# ArduinoInterface.net
KiCad netlist of a schematic drawn in EAGLE
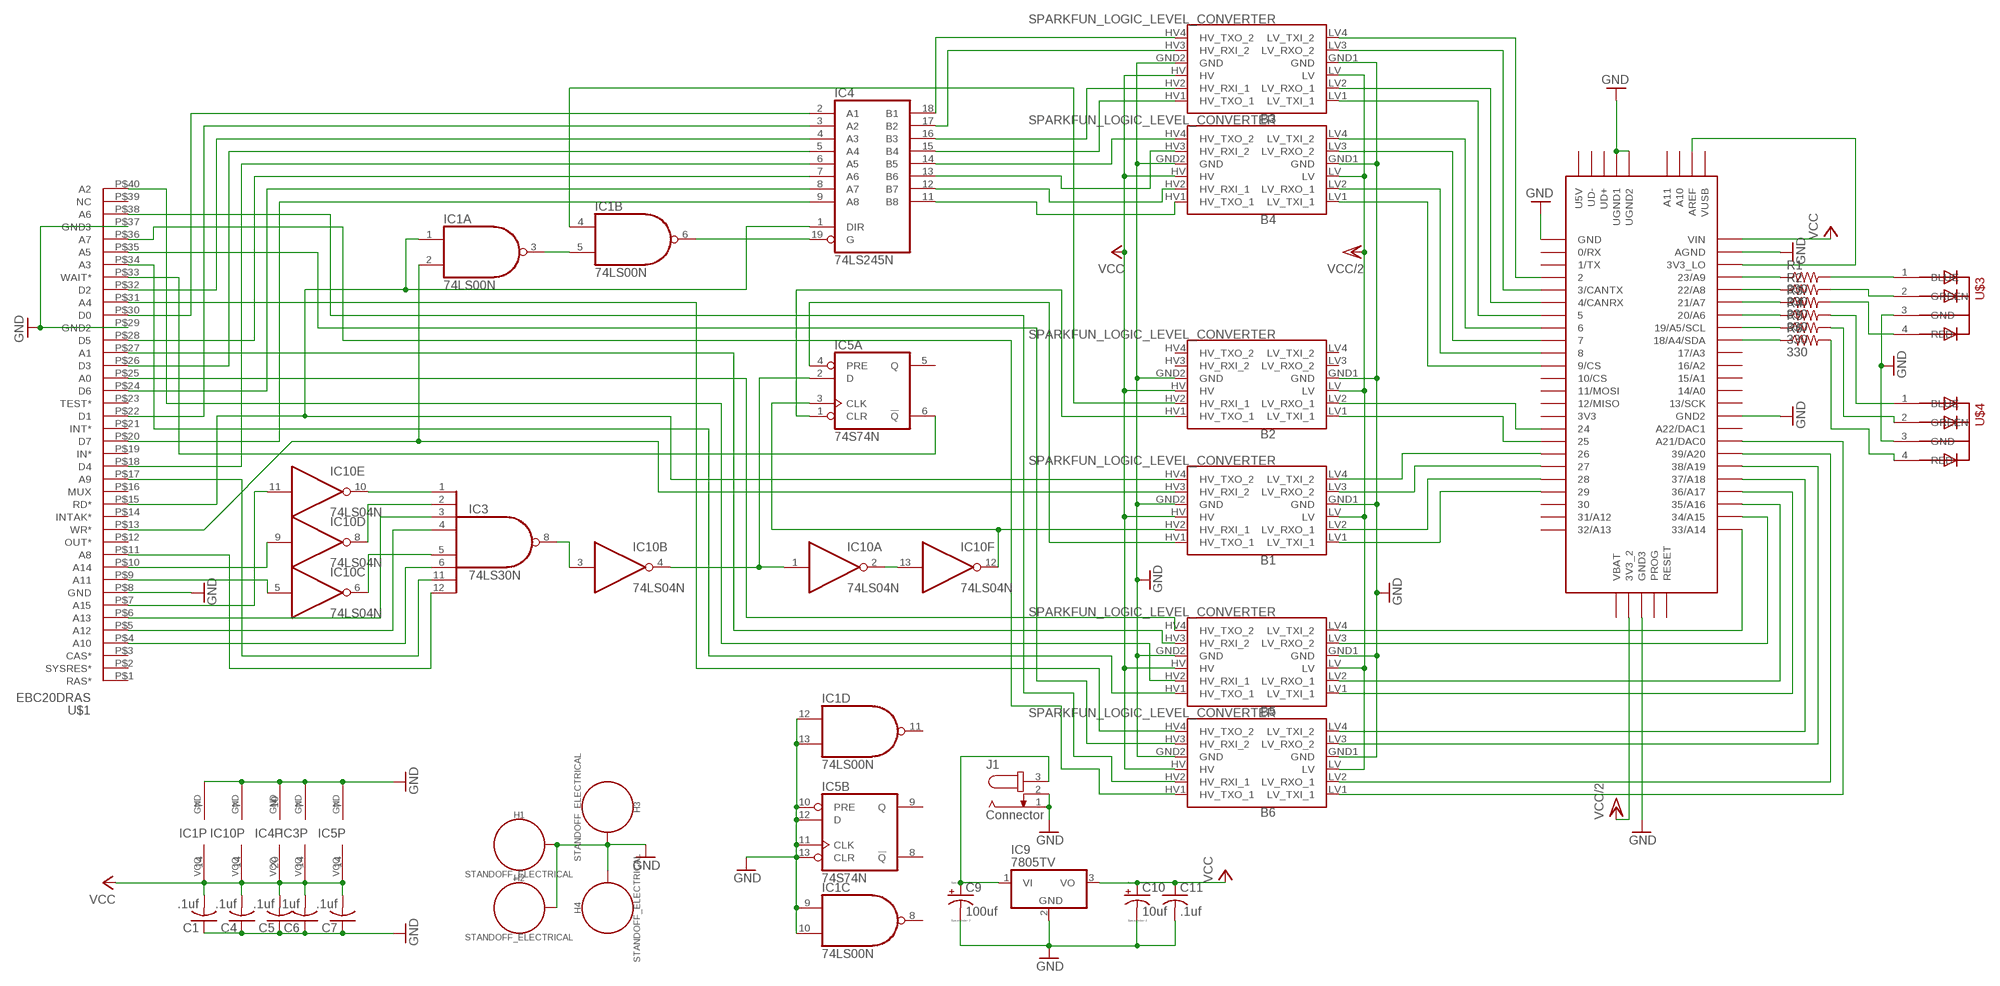
[diagram p0: schematic, sheet 1]

(export (version "E")
  (design (tool "Eeschema 10.0.6"))
  (components
    (comp (ref "B1")
      (value "SPARKFUN_LOGIC_LEVEL_CONVERTER")
      (footprint "eagle-import:SPARKFUN_LOGIC_LEVEL_CONVERTER")
      (libsource (lib "eagle-import") (part "SPARKFUN_LOGIC_LEVEL_CONVERTER"))
    )
    (comp (ref "B2")
      (value "SPARKFUN_LOGIC_LEVEL_CONVERTER")
      (footprint "eagle-import:SPARKFUN_LOGIC_LEVEL_CONVERTER")
      (libsource (lib "eagle-import") (part "SPARKFUN_LOGIC_LEVEL_CONVERTER"))
    )
    (comp (ref "B3")
      (value "SPARKFUN_LOGIC_LEVEL_CONVERTER")
      (footprint "eagle-import:SPARKFUN_LOGIC_LEVEL_CONVERTER")
      (libsource (lib "eagle-import") (part "SPARKFUN_LOGIC_LEVEL_CONVERTER"))
    )
    (comp (ref "B4")
      (value "SPARKFUN_LOGIC_LEVEL_CONVERTER")
      (footprint "eagle-import:SPARKFUN_LOGIC_LEVEL_CONVERTER")
      (libsource (lib "eagle-import") (part "SPARKFUN_LOGIC_LEVEL_CONVERTER"))
    )
    (comp (ref "B5")
      (value "SPARKFUN_LOGIC_LEVEL_CONVERTER")
      (footprint "eagle-import:SPARKFUN_LOGIC_LEVEL_CONVERTER")
      (libsource (lib "eagle-import") (part "SPARKFUN_LOGIC_LEVEL_CONVERTER"))
    )
    (comp (ref "B6")
      (value "SPARKFUN_LOGIC_LEVEL_CONVERTER")
      (footprint "eagle-import:SPARKFUN_LOGIC_LEVEL_CONVERTER")
      (libsource (lib "eagle-import") (part "SPARKFUN_LOGIC_LEVEL_CONVERTER"))
    )
    (comp (ref "C1")
      (value ".1uf")
      (footprint "eagle-import:C025-025X050")
      (libsource (lib "eagle-import") (part "C-US025-025X050"))
    )
    (comp (ref "C4")
      (value ".1uf")
      (footprint "eagle-import:C025-025X050")
      (libsource (lib "eagle-import") (part "C-US025-025X050"))
    )
    (comp (ref "C5")
      (value ".1uf")
      (footprint "eagle-import:C025-025X050")
      (libsource (lib "eagle-import") (part "C-US025-025X050"))
    )
    (comp (ref "C6")
      (value ".1uf")
      (footprint "eagle-import:C025-025X050")
      (libsource (lib "eagle-import") (part "C-US025-025X050"))
    )
    (comp (ref "C7")
      (value ".1uf")
      (footprint "eagle-import:C025-025X050")
      (libsource (lib "eagle-import") (part "C-US025-025X050"))
    )
    (comp (ref "C9")
      (value "100uf")
      (footprint "eagle-import:E5-6")
      (libsource (lib "eagle-import") (part "CPOL-USE5-6"))
    )
    (comp (ref "C10")
      (value "10uf")
      (footprint "eagle-import:E5-6")
      (libsource (lib "eagle-import") (part "CPOL-USE5-6"))
    )
    (comp (ref "C11")
      (value ".1uf")
      (footprint "eagle-import:C025-025X050")
      (libsource (lib "eagle-import") (part "C-US025-025X050"))
    )
    (comp (ref "H1")
      (value "STANDOFF_ELECTRICAL")
      (footprint "eagle-import:STANDOFF-ELECTRICAL")
      (libsource (lib "eagle-import") (part "STANDOFF_ELECTRICAL"))
    )
    (comp (ref "H2")
      (value "STANDOFF_ELECTRICAL")
      (footprint "eagle-import:STANDOFF-ELECTRICAL")
      (libsource (lib "eagle-import") (part "STANDOFF_ELECTRICAL"))
    )
    (comp (ref "H3")
      (value "STANDOFF_ELECTRICAL")
      (footprint "eagle-import:STANDOFF-ELECTRICAL")
      (libsource (lib "eagle-import") (part "STANDOFF_ELECTRICAL"))
    )
    (comp (ref "H4")
      (value "STANDOFF_ELECTRICAL")
      (footprint "eagle-import:STANDOFF-ELECTRICAL")
      (libsource (lib "eagle-import") (part "STANDOFF_ELECTRICAL"))
    )
    (comp (ref "IC1")
      (value "74LS00N")
      (footprint "eagle-import:DIL14")
      (libsource (lib "eagle-import") (part "7400NLS"))
    )
    (comp (ref "IC3")
      (value "74LS30N")
      (footprint "eagle-import:DIL14")
      (libsource (lib "eagle-import") (part "7430NLS"))
    )
    (comp (ref "IC4")
      (value "74LS245N")
      (footprint "eagle-import:DIL20")
      (libsource (lib "eagle-import") (part "74245NLS"))
    )
    (comp (ref "IC5")
      (value "74S74N")
      (footprint "eagle-import:DIL14")
      (libsource (lib "eagle-import") (part "7474NS"))
    )
    (comp (ref "IC9")
      (value "7805TV")
      (footprint "eagle-import:TO220V")
      (libsource (lib "eagle-import") (part "78TV05"))
    )
    (comp (ref "IC10")
      (value "74LS04N")
      (footprint "eagle-import:DIL14")
      (libsource (lib "eagle-import") (part "7404NLS"))
    )
    (comp (ref "J1")
      (value "Connector")
      (footprint "eagle-import:SPC4077")
      (libsource (lib "eagle-import") (part "JACK-PLUG0"))
    )
    (comp (ref "R1")
      (value "330")
      (footprint "eagle-import:0204V")
      (libsource (lib "eagle-import") (part "R-US_0204/2V"))
    )
    (comp (ref "R2")
      (value "330")
      (footprint "eagle-import:0204V")
      (libsource (lib "eagle-import") (part "R-US_0204/2V"))
    )
    (comp (ref "R3")
      (value "330")
      (footprint "eagle-import:0204V")
      (libsource (lib "eagle-import") (part "R-US_0204/2V"))
    )
    (comp (ref "R4")
      (value "330")
      (footprint "eagle-import:0204V")
      (libsource (lib "eagle-import") (part "R-US_0204/2V"))
    )
    (comp (ref "R5")
      (value "330")
      (footprint "eagle-import:0204V")
      (libsource (lib "eagle-import") (part "R-US_0204/2V"))
    )
    (comp (ref "R6")
      (value "330")
      (footprint "eagle-import:0204V")
      (libsource (lib "eagle-import") (part "R-US_0204/2V"))
    )
    (comp (ref "U$1")
      (value "EBC20DRAS")
      (footprint "eagle-import:EBC20DRAS")
      (libsource (lib "eagle-import") (part "EBC20DRAS"))
    )
    (comp (ref "U$2")
      (value "TEENSY_3.5/3.6")
      (footprint "eagle-import:TEENSY_3.5_3.6")
      (libsource (lib "eagle-import") (part "TEENSY_3.5/3.6"))
    )
    (comp (ref "U$3")
      (value "5MMRGBLED")
      (footprint "eagle-import:LED5MMRGB")
      (libsource (lib "eagle-import") (part "5MMRGBLED"))
    )
    (comp (ref "U$4")
      (value "5MMRGBLED")
      (footprint "eagle-import:LED5MMRGB")
      (libsource (lib "eagle-import") (part "5MMRGBLED"))
    )
  )
  (nets
    (net (code "1") (name "GND") (class "Default")
      (node (ref "B1") (pin "GND1") (pinfunction "GND_GND1") (pintype "power_in"))
      (node (ref "B1") (pin "GND2") (pinfunction "GND_GND2") (pintype "power_in"))
      (node (ref "B2") (pin "GND1") (pinfunction "GND_GND1") (pintype "power_in"))
      (node (ref "B2") (pin "GND2") (pinfunction "GND_GND2") (pintype "power_in"))
      (node (ref "B3") (pin "GND1") (pinfunction "GND_GND1") (pintype "power_in"))
      (node (ref "B3") (pin "GND2") (pinfunction "GND_GND2") (pintype "power_in"))
      (node (ref "B4") (pin "GND1") (pinfunction "GND_GND1") (pintype "power_in"))
      (node (ref "B4") (pin "GND2") (pinfunction "GND_GND2") (pintype "power_in"))
      (node (ref "B5") (pin "GND1") (pinfunction "GND_GND1") (pintype "power_in"))
      (node (ref "B5") (pin "GND2") (pinfunction "GND_GND2") (pintype "power_in"))
      (node (ref "B6") (pin "GND1") (pinfunction "GND_GND1") (pintype "power_in"))
      (node (ref "B6") (pin "GND2") (pinfunction "GND_GND2") (pintype "power_in"))
      (node (ref "C1") (pin "1") (pinfunction "1_1") (pintype "passive"))
      (node (ref "C10") (pin "-") (pinfunction "-_-") (pintype "passive"))
      (node (ref "C11") (pin "2") (pinfunction "2_2") (pintype "passive"))
      (node (ref "C4") (pin "1") (pinfunction "1_1") (pintype "passive"))
      (node (ref "C5") (pin "1") (pinfunction "1_1") (pintype "passive"))
      (node (ref "C6") (pin "1") (pinfunction "1_1") (pintype "passive"))
      (node (ref "C7") (pin "1") (pinfunction "1_1") (pintype "passive"))
      (node (ref "C9") (pin "-") (pinfunction "-_-") (pintype "passive"))
      (node (ref "H1") (pin "P1") (pinfunction "P$1_P1") (pintype "bidirectional"))
      (node (ref "H2") (pin "P1") (pinfunction "P$1_P1") (pintype "bidirectional"))
      (node (ref "H3") (pin "P1") (pinfunction "P$1_P1") (pintype "bidirectional"))
      (node (ref "H4") (pin "P1") (pinfunction "P$1_P1") (pintype "bidirectional"))
      (node (ref "IC1") (pin "10") (pinfunction "I1_10") (pintype "input"))
      (node (ref "IC1") (pin "12") (pinfunction "I0_12") (pintype "input"))
      (node (ref "IC1") (pin "13") (pinfunction "I1_13") (pintype "input"))
      (node (ref "IC1") (pin "7") (pinfunction "GND_7") (pintype "power_in"))
      (node (ref "IC1") (pin "9") (pinfunction "I0_9") (pintype "input"))
      (node (ref "IC10") (pin "7") (pinfunction "GND_7") (pintype "power_in"))
      (node (ref "IC3") (pin "7") (pinfunction "GND_7") (pintype "power_in"))
      (node (ref "IC4") (pin "10") (pinfunction "GND_10") (pintype "power_in"))
      (node (ref "IC5") (pin "10") (pinfunction "PRE_10") (pintype "input"))
      (node (ref "IC5") (pin "11") (pinfunction "CLK_11") (pintype "input"))
      (node (ref "IC5") (pin "12") (pinfunction "D_12") (pintype "input"))
      (node (ref "IC5") (pin "13") (pinfunction "CLR_13") (pintype "input"))
      (node (ref "IC5") (pin "7") (pinfunction "GND_7") (pintype "power_in"))
      (node (ref "IC9") (pin "2") (pinfunction "GND_2") (pintype "passive"))
      (node (ref "J1") (pin "1") (pinfunction "1_1") (pintype "passive"))
      (node (ref "J1") (pin "2") (pinfunction "2_2") (pintype "passive"))
      (node (ref "U$1") (pin "P$29") (pinfunction "GND2_P$29") (pintype "bidirectional"))
      (node (ref "U$1") (pin "P$37") (pinfunction "GND3_P$37") (pintype "bidirectional"))
      (node (ref "U$1") (pin "P$8") (pinfunction "GND_P$8") (pintype "bidirectional"))
      (node (ref "U$2") (pin "AGND") (pinfunction "AGND_AGND") (pintype "bidirectional"))
      (node (ref "U$2") (pin "GND") (pinfunction "GND_GND") (pintype "bidirectional"))
      (node (ref "U$2") (pin "GND2") (pinfunction "GND2_GND2") (pintype "bidirectional"))
      (node (ref "U$2") (pin "GND3") (pinfunction "GND3_GND3") (pintype "bidirectional"))
      (node (ref "U$2") (pin "UGND1") (pinfunction "UGND1_UGND1") (pintype "bidirectional"))
      (node (ref "U$2") (pin "UGND2") (pinfunction "UGND2_UGND2") (pintype "bidirectional"))
      (node (ref "U$3") (pin "3") (pinfunction "GND_3") (pintype "bidirectional"))
      (node (ref "U$4") (pin "3") (pinfunction "GND_3") (pintype "bidirectional"))
    )
    (net (code "2") (name "Net-(B1-HV_RXI_1)") (class "Default")
      (node (ref "B1") (pin "HV2") (pinfunction "HV_RXI_1_HV2") (pintype "bidirectional"))
      (node (ref "IC10") (pin "12") (pinfunction "O_12") (pintype "output"))
      (node (ref "IC5") (pin "3") (pinfunction "CLK_3") (pintype "input"))
    )
    (net (code "3") (name "Net-(B1-HV_RXI_2)") (class "Default")
      (node (ref "B1") (pin "HV3") (pinfunction "HV_RXI_2_HV3") (pintype "bidirectional"))
      (node (ref "IC1") (pin "2") (pinfunction "I1_2") (pintype "input"))
      (node (ref "U$1") (pin "P$13") (pinfunction "WR*_P$13") (pintype "bidirectional"))
    )
    (net (code "4") (name "Net-(B1-HV_TXO_1)") (class "Default")
      (node (ref "B1") (pin "HV1") (pinfunction "HV_TXO_1_HV1") (pintype "bidirectional"))
      (node (ref "IC5") (pin "4") (pinfunction "PRE_4") (pintype "input"))
    )
    (net (code "5") (name "Net-(B1-HV_TXO_2)") (class "Default")
      (node (ref "B1") (pin "HV4") (pinfunction "HV_TXO_2_HV4") (pintype "bidirectional"))
      (node (ref "IC1") (pin "1") (pinfunction "I0_1") (pintype "input"))
      (node (ref "IC4") (pin "1") (pinfunction "DIR_1") (pintype "input"))
      (node (ref "U$1") (pin "P$15") (pinfunction "RD*_P$15") (pintype "bidirectional"))
    )
    (net (code "6") (name "Net-(B1-LV_RXO_1)") (class "Default")
      (node (ref "B1") (pin "LV2") (pinfunction "LV_RXO_1_LV2") (pintype "bidirectional"))
      (node (ref "U$2") (pin "28") (pinfunction "28_28") (pintype "bidirectional"))
    )
    (net (code "7") (name "Net-(B1-LV_RXO_2)") (class "Default")
      (node (ref "B1") (pin "LV3") (pinfunction "LV_RXO_2_LV3") (pintype "bidirectional"))
      (node (ref "U$2") (pin "27") (pinfunction "27_27") (pintype "bidirectional"))
    )
    (net (code "8") (name "Net-(B1-LV_TXI_1)") (class "Default")
      (node (ref "B1") (pin "LV1") (pinfunction "LV_TXI_1_LV1") (pintype "bidirectional"))
      (node (ref "U$2") (pin "29") (pinfunction "29_29") (pintype "bidirectional"))
    )
    (net (code "9") (name "Net-(B1-LV_TXI_2)") (class "Default")
      (node (ref "B1") (pin "LV4") (pinfunction "LV_TXI_2_LV4") (pintype "bidirectional"))
      (node (ref "U$2") (pin "26") (pinfunction "26_26") (pintype "bidirectional"))
    )
    (net (code "10") (name "Net-(B2-HV_RXI_1)") (class "Default")
      (node (ref "B2") (pin "HV2") (pinfunction "HV_RXI_1_HV2") (pintype "bidirectional"))
      (node (ref "IC1") (pin "4") (pinfunction "I0_4") (pintype "input"))
    )
    (net (code "11") (name "Net-(B2-HV_TXO_1)") (class "Default")
      (node (ref "B2") (pin "HV1") (pinfunction "HV_TXO_1_HV1") (pintype "bidirectional"))
      (node (ref "IC5") (pin "1") (pinfunction "CLR_1") (pintype "input"))
    )
    (net (code "12") (name "Net-(B2-LV_RXO_1)") (class "Default")
      (node (ref "B2") (pin "LV2") (pinfunction "LV_RXO_1_LV2") (pintype "bidirectional"))
      (node (ref "U$2") (pin "24") (pinfunction "24_24") (pintype "bidirectional"))
    )
    (net (code "13") (name "Net-(B2-LV_TXI_1)") (class "Default")
      (node (ref "B2") (pin "LV1") (pinfunction "LV_TXI_1_LV1") (pintype "bidirectional"))
      (node (ref "U$2") (pin "25") (pinfunction "25_25") (pintype "bidirectional"))
    )
    (net (code "14") (name "Net-(B3-HV_RXI_1)") (class "Default")
      (node (ref "B3") (pin "HV2") (pinfunction "HV_RXI_1_HV2") (pintype "bidirectional"))
      (node (ref "IC4") (pin "16") (pinfunction "B3_16") (pintype "bidirectional"))
    )
    (net (code "15") (name "Net-(B3-HV_RXI_2)") (class "Default")
      (node (ref "B3") (pin "HV3") (pinfunction "HV_RXI_2_HV3") (pintype "bidirectional"))
      (node (ref "IC4") (pin "17") (pinfunction "B2_17") (pintype "bidirectional"))
    )
    (net (code "16") (name "Net-(B3-HV_TXO_1)") (class "Default")
      (node (ref "B3") (pin "HV1") (pinfunction "HV_TXO_1_HV1") (pintype "bidirectional"))
      (node (ref "IC4") (pin "15") (pinfunction "B4_15") (pintype "bidirectional"))
    )
    (net (code "17") (name "Net-(B3-HV_TXO_2)") (class "Default")
      (node (ref "B3") (pin "HV4") (pinfunction "HV_TXO_2_HV4") (pintype "bidirectional"))
      (node (ref "IC4") (pin "18") (pinfunction "B1_18") (pintype "bidirectional"))
    )
    (net (code "18") (name "Net-(B3-LV_RXO_1)") (class "Default")
      (node (ref "B3") (pin "LV2") (pinfunction "LV_RXO_1_LV2") (pintype "bidirectional"))
      (node (ref "U$2") (pin "4/CANRX") (pinfunction "4/CANRX_4/CANRX") (pintype "bidirectional"))
    )
    (net (code "19") (name "Net-(B3-LV_RXO_2)") (class "Default")
      (node (ref "B3") (pin "LV3") (pinfunction "LV_RXO_2_LV3") (pintype "bidirectional"))
      (node (ref "U$2") (pin "3/CANTX") (pinfunction "3/CANTX_3/CANTX") (pintype "bidirectional"))
    )
    (net (code "20") (name "Net-(B3-LV_TXI_1)") (class "Default")
      (node (ref "B3") (pin "LV1") (pinfunction "LV_TXI_1_LV1") (pintype "bidirectional"))
      (node (ref "U$2") (pin "5") (pinfunction "5_5") (pintype "bidirectional"))
    )
    (net (code "21") (name "Net-(B3-LV_TXI_2)") (class "Default")
      (node (ref "B3") (pin "LV4") (pinfunction "LV_TXI_2_LV4") (pintype "bidirectional"))
      (node (ref "U$2") (pin "2") (pinfunction "2_2") (pintype "bidirectional"))
    )
    (net (code "22") (name "Net-(B4-HV_RXI_1)") (class "Default")
      (node (ref "B4") (pin "HV2") (pinfunction "HV_RXI_1_HV2") (pintype "bidirectional"))
      (node (ref "IC4") (pin "12") (pinfunction "B7_12") (pintype "bidirectional"))
    )
    (net (code "23") (name "Net-(B4-HV_RXI_2)") (class "Default")
      (node (ref "B4") (pin "HV3") (pinfunction "HV_RXI_2_HV3") (pintype "bidirectional"))
      (node (ref "IC4") (pin "13") (pinfunction "B6_13") (pintype "bidirectional"))
    )
    (net (code "24") (name "Net-(B4-HV_TXO_1)") (class "Default")
      (node (ref "B4") (pin "HV1") (pinfunction "HV_TXO_1_HV1") (pintype "bidirectional"))
      (node (ref "IC4") (pin "11") (pinfunction "B8_11") (pintype "bidirectional"))
    )
    (net (code "25") (name "Net-(B4-HV_TXO_2)") (class "Default")
      (node (ref "B4") (pin "HV4") (pinfunction "HV_TXO_2_HV4") (pintype "bidirectional"))
      (node (ref "IC4") (pin "14") (pinfunction "B5_14") (pintype "bidirectional"))
    )
    (net (code "26") (name "Net-(B4-LV_RXO_1)") (class "Default")
      (node (ref "B4") (pin "LV2") (pinfunction "LV_RXO_1_LV2") (pintype "bidirectional"))
      (node (ref "U$2") (pin "8") (pinfunction "8_8") (pintype "bidirectional"))
    )
    (net (code "27") (name "Net-(B4-LV_RXO_2)") (class "Default")
      (node (ref "B4") (pin "LV3") (pinfunction "LV_RXO_2_LV3") (pintype "bidirectional"))
      (node (ref "U$2") (pin "7") (pinfunction "7_7") (pintype "bidirectional"))
    )
    (net (code "28") (name "Net-(B4-LV_TXI_1)") (class "Default")
      (node (ref "B4") (pin "LV1") (pinfunction "LV_TXI_1_LV1") (pintype "bidirectional"))
      (node (ref "U$2") (pin "9/CS") (pinfunction "9/CS_9/CS") (pintype "bidirectional"))
    )
    (net (code "29") (name "Net-(B4-LV_TXI_2)") (class "Default")
      (node (ref "B4") (pin "LV4") (pinfunction "LV_TXI_2_LV4") (pintype "bidirectional"))
      (node (ref "U$2") (pin "6") (pinfunction "6_6") (pintype "bidirectional"))
    )
    (net (code "30") (name "Net-(B5-HV_RXI_1)") (class "Default")
      (node (ref "B5") (pin "HV2") (pinfunction "HV_RXI_1_HV2") (pintype "bidirectional"))
      (node (ref "U$1") (pin "P$40") (pinfunction "A2_P$40") (pintype "bidirectional"))
    )
    (net (code "31") (name "Net-(B5-HV_RXI_2)") (class "Default")
      (node (ref "B5") (pin "HV3") (pinfunction "HV_RXI_2_HV3") (pintype "bidirectional"))
      (node (ref "U$1") (pin "P$27") (pinfunction "A1_P$27") (pintype "bidirectional"))
    )
    (net (code "32") (name "Net-(B5-HV_TXO_1)") (class "Default")
      (node (ref "B5") (pin "HV1") (pinfunction "HV_TXO_1_HV1") (pintype "bidirectional"))
      (node (ref "U$1") (pin "P$34") (pinfunction "A3_P$34") (pintype "bidirectional"))
    )
    (net (code "33") (name "Net-(B5-HV_TXO_2)") (class "Default")
      (node (ref "B5") (pin "HV4") (pinfunction "HV_TXO_2_HV4") (pintype "bidirectional"))
      (node (ref "U$1") (pin "P$25") (pinfunction "A0_P$25") (pintype "bidirectional"))
    )
    (net (code "34") (name "Net-(B5-LV_RXO_1)") (class "Default")
      (node (ref "B5") (pin "LV2") (pinfunction "LV_RXO_1_LV2") (pintype "bidirectional"))
      (node (ref "U$2") (pin "35/A16") (pinfunction "35/A16_35/A16") (pintype "bidirectional"))
    )
    (net (code "35") (name "Net-(B5-LV_RXO_2)") (class "Default")
      (node (ref "B5") (pin "LV3") (pinfunction "LV_RXO_2_LV3") (pintype "bidirectional"))
      (node (ref "U$2") (pin "34/A15") (pinfunction "34/A15_34/A15") (pintype "bidirectional"))
    )
    (net (code "36") (name "Net-(B5-LV_TXI_1)") (class "Default")
      (node (ref "B5") (pin "LV1") (pinfunction "LV_TXI_1_LV1") (pintype "bidirectional"))
      (node (ref "U$2") (pin "36/A17") (pinfunction "36/A17_36/A17") (pintype "bidirectional"))
    )
    (net (code "37") (name "Net-(B5-LV_TXI_2)") (class "Default")
      (node (ref "B5") (pin "LV4") (pinfunction "LV_TXI_2_LV4") (pintype "bidirectional"))
      (node (ref "U$2") (pin "33/A14") (pinfunction "33/A14_33/A14") (pintype "bidirectional"))
    )
    (net (code "38") (name "Net-(B6-HV_RXI_1)") (class "Default")
      (node (ref "B6") (pin "HV2") (pinfunction "HV_RXI_1_HV2") (pintype "bidirectional"))
      (node (ref "U$1") (pin "P$38") (pinfunction "A6_P$38") (pintype "bidirectional"))
    )
    (net (code "39") (name "Net-(B6-HV_RXI_2)") (class "Default")
      (node (ref "B6") (pin "HV3") (pinfunction "HV_RXI_2_HV3") (pintype "bidirectional"))
      (node (ref "U$1") (pin "P$35") (pinfunction "A5_P$35") (pintype "bidirectional"))
    )
    (net (code "40") (name "Net-(B6-HV_TXO_1)") (class "Default")
      (node (ref "B6") (pin "HV1") (pinfunction "HV_TXO_1_HV1") (pintype "bidirectional"))
      (node (ref "U$1") (pin "P$36") (pinfunction "A7_P$36") (pintype "bidirectional"))
    )
    (net (code "41") (name "Net-(B6-HV_TXO_2)") (class "Default")
      (node (ref "B6") (pin "HV4") (pinfunction "HV_TXO_2_HV4") (pintype "bidirectional"))
      (node (ref "U$1") (pin "P$31") (pinfunction "A4_P$31") (pintype "bidirectional"))
    )
    (net (code "42") (name "Net-(B6-LV_RXO_1)") (class "Default")
      (node (ref "B6") (pin "LV2") (pinfunction "LV_RXO_1_LV2") (pintype "bidirectional"))
      (node (ref "U$2") (pin "39/A20") (pinfunction "39/A20_39/A20") (pintype "bidirectional"))
    )
    (net (code "43") (name "Net-(B6-LV_RXO_2)") (class "Default")
      (node (ref "B6") (pin "LV3") (pinfunction "LV_RXO_2_LV3") (pintype "bidirectional"))
      (node (ref "U$2") (pin "38/A19") (pinfunction "38/A19_38/A19") (pintype "bidirectional"))
    )
    (net (code "44") (name "Net-(B6-LV_TXI_1)") (class "Default")
      (node (ref "B6") (pin "LV1") (pinfunction "LV_TXI_1_LV1") (pintype "bidirectional"))
      (node (ref "U$2") (pin "21/DAC0") (pinfunction "A21/DAC0_21/DAC0") (pintype "bidirectional"))
    )
    (net (code "45") (name "Net-(B6-LV_TXI_2)") (class "Default")
      (node (ref "B6") (pin "LV4") (pinfunction "LV_TXI_2_LV4") (pintype "bidirectional"))
      (node (ref "U$2") (pin "37/A18") (pinfunction "37/A18_37/A18") (pintype "bidirectional"))
    )
    (net (code "46") (name "Net-(IC1A-O)") (class "Default")
      (node (ref "IC1") (pin "3") (pinfunction "O_3") (pintype "output"))
      (node (ref "IC1") (pin "5") (pinfunction "I1_5") (pintype "input"))
    )
    (net (code "47") (name "Net-(IC1B-O)") (class "Default")
      (node (ref "IC1") (pin "6") (pinfunction "O_6") (pintype "output"))
      (node (ref "IC4") (pin "19") (pinfunction "G_19") (pintype "input"))
    )
    (net (code "48") (name "Net-(IC3A-I2)") (class "Default")
      (node (ref "IC3") (pin "3") (pinfunction "I2_3") (pintype "input"))
      (node (ref "U$1") (pin "P$6") (pinfunction "A13_P$6") (pintype "bidirectional"))
    )
    (net (code "49") (name "Net-(IC3A-I3)") (class "Default")
      (node (ref "IC3") (pin "4") (pinfunction "I3_4") (pintype "input"))
      (node (ref "U$1") (pin "P$5") (pinfunction "A12_P$5") (pintype "bidirectional"))
    )
    (net (code "50") (name "Net-(IC3A-I5)") (class "Default")
      (node (ref "IC3") (pin "6") (pinfunction "I5_6") (pintype "input"))
      (node (ref "U$1") (pin "P$4") (pinfunction "A10_P$4") (pintype "bidirectional"))
    )
    (net (code "51") (name "Net-(IC3A-I6)") (class "Default")
      (node (ref "IC3") (pin "11") (pinfunction "I6_11") (pintype "input"))
      (node (ref "U$1") (pin "P$17") (pinfunction "A9_P$17") (pintype "bidirectional"))
    )
    (net (code "52") (name "Net-(IC3A-I7)") (class "Default")
      (node (ref "IC3") (pin "12") (pinfunction "I7_12") (pintype "input"))
      (node (ref "U$1") (pin "P$11") (pinfunction "A8_P$11") (pintype "bidirectional"))
    )
    (net (code "53") (name "Net-(IC4A-A1)") (class "Default")
      (node (ref "IC4") (pin "2") (pinfunction "A1_2") (pintype "bidirectional"))
      (node (ref "U$1") (pin "P$30") (pinfunction "D0_P$30") (pintype "bidirectional"))
    )
    (net (code "54") (name "Net-(IC4A-A2)") (class "Default")
      (node (ref "IC4") (pin "3") (pinfunction "A2_3") (pintype "bidirectional"))
      (node (ref "U$1") (pin "P$22") (pinfunction "D1_P$22") (pintype "bidirectional"))
    )
    (net (code "55") (name "Net-(IC4A-A3)") (class "Default")
      (node (ref "IC4") (pin "4") (pinfunction "A3_4") (pintype "bidirectional"))
      (node (ref "U$1") (pin "P$32") (pinfunction "D2_P$32") (pintype "bidirectional"))
    )
    (net (code "56") (name "Net-(IC4A-A4)") (class "Default")
      (node (ref "IC4") (pin "5") (pinfunction "A4_5") (pintype "bidirectional"))
      (node (ref "U$1") (pin "P$26") (pinfunction "D3_P$26") (pintype "bidirectional"))
    )
    (net (code "57") (name "Net-(IC4A-A5)") (class "Default")
      (node (ref "IC4") (pin "6") (pinfunction "A5_6") (pintype "bidirectional"))
      (node (ref "U$1") (pin "P$18") (pinfunction "D4_P$18") (pintype "bidirectional"))
    )
    (net (code "58") (name "Net-(IC4A-A6)") (class "Default")
      (node (ref "IC4") (pin "7") (pinfunction "A6_7") (pintype "bidirectional"))
      (node (ref "U$1") (pin "P$28") (pinfunction "D5_P$28") (pintype "bidirectional"))
    )
    (net (code "59") (name "Net-(IC4A-A7)") (class "Default")
      (node (ref "IC4") (pin "8") (pinfunction "A7_8") (pintype "bidirectional"))
      (node (ref "U$1") (pin "P$24") (pinfunction "D6_P$24") (pintype "bidirectional"))
    )
    (net (code "60") (name "Net-(IC4A-A8)") (class "Default")
      (node (ref "IC4") (pin "9") (pinfunction "A8_9") (pintype "bidirectional"))
      (node (ref "U$1") (pin "P$20") (pinfunction "D7_P$20") (pintype "bidirectional"))
    )
    (net (code "61") (name "Net-(IC5A-~{Q})") (class "Default")
      (node (ref "IC5") (pin "6") (pinfunction "~{Q}_6") (pintype "output"))
      (node (ref "U$1") (pin "P$33") (pinfunction "WAIT*_P$33") (pintype "bidirectional"))
    )
    (net (code "62") (name "Net-(IC9-VI)") (class "Default")
      (node (ref "C9") (pin "+") (pinfunction "+_+") (pintype "passive"))
      (node (ref "IC9") (pin "1") (pinfunction "VI_1") (pintype "input"))
      (node (ref "J1") (pin "3") (pinfunction "3_3") (pintype "passive"))
    )
    (net (code "63") (name "Net-(IC10A-I)") (class "Default")
      (node (ref "IC10") (pin "1") (pinfunction "I_1") (pintype "input"))
      (node (ref "IC10") (pin "4") (pinfunction "O_4") (pintype "output"))
      (node (ref "IC5") (pin "2") (pinfunction "D_2") (pintype "input"))
    )
    (net (code "64") (name "Net-(IC10A-O)") (class "Default")
      (node (ref "IC10") (pin "13") (pinfunction "I_13") (pintype "input"))
      (node (ref "IC10") (pin "2") (pinfunction "O_2") (pintype "output"))
    )
    (net (code "65") (name "Net-(IC10B-I)") (class "Default")
      (node (ref "IC10") (pin "3") (pinfunction "I_3") (pintype "input"))
      (node (ref "IC3") (pin "8") (pinfunction "O_8") (pintype "output"))
    )
    (net (code "66") (name "Net-(IC10C-I)") (class "Default")
      (node (ref "IC10") (pin "5") (pinfunction "I_5") (pintype "input"))
      (node (ref "U$1") (pin "P$9") (pinfunction "A11_P$9") (pintype "bidirectional"))
    )
    (net (code "67") (name "Net-(IC10C-O)") (class "Default")
      (node (ref "IC10") (pin "6") (pinfunction "O_6") (pintype "output"))
      (node (ref "IC3") (pin "5") (pinfunction "I4_5") (pintype "input"))
    )
    (net (code "68") (name "Net-(IC10D-I)") (class "Default")
      (node (ref "IC10") (pin "9") (pinfunction "I_9") (pintype "input"))
      (node (ref "U$1") (pin "P$10") (pinfunction "A14_P$10") (pintype "bidirectional"))
    )
    (net (code "69") (name "Net-(IC10D-O)") (class "Default")
      (node (ref "IC10") (pin "8") (pinfunction "O_8") (pintype "output"))
      (node (ref "IC3") (pin "2") (pinfunction "I1_2") (pintype "input"))
    )
    (net (code "70") (name "Net-(IC10E-I)") (class "Default")
      (node (ref "IC10") (pin "11") (pinfunction "I_11") (pintype "input"))
      (node (ref "U$1") (pin "P$7") (pinfunction "A15_P$7") (pintype "bidirectional"))
    )
    (net (code "71") (name "Net-(IC10E-O)") (class "Default")
      (node (ref "IC10") (pin "10") (pinfunction "O_10") (pintype "output"))
      (node (ref "IC3") (pin "1") (pinfunction "I0_1") (pintype "input"))
    )
    (net (code "72") (name "Net-(R1-Pad1)") (class "Default")
      (node (ref "R1") (pin "1") (pinfunction "1_1") (pintype "passive"))
      (node (ref "U$2") (pin "23/A9") (pinfunction "23/A9_23/A9") (pintype "bidirectional"))
    )
    (net (code "73") (name "Net-(R2-Pad1)") (class "Default")
      (node (ref "R2") (pin "1") (pinfunction "1_1") (pintype "passive"))
      (node (ref "U$2") (pin "22/A8") (pinfunction "22/A8_22/A8") (pintype "bidirectional"))
    )
    (net (code "74") (name "Net-(R3-Pad1)") (class "Default")
      (node (ref "R3") (pin "1") (pinfunction "1_1") (pintype "passive"))
      (node (ref "U$2") (pin "21/A7") (pinfunction "21/A7_21/A7") (pintype "bidirectional"))
    )
    (net (code "75") (name "Net-(R4-Pad1)") (class "Default")
      (node (ref "R4") (pin "1") (pinfunction "1_1") (pintype "passive"))
      (node (ref "U$2") (pin "20/A6") (pinfunction "20/A6_20/A6") (pintype "bidirectional"))
    )
    (net (code "76") (name "Net-(R5-Pad1)") (class "Default")
      (node (ref "R5") (pin "1") (pinfunction "1_1") (pintype "passive"))
      (node (ref "U$2") (pin "19/A5/SCL") (pinfunction "19/A5/SCL_19/A5/SCL") (pintype "bidirectional"))
    )
    (net (code "77") (name "Net-(R6-Pad1)") (class "Default")
      (node (ref "R6") (pin "1") (pinfunction "1_1") (pintype "passive"))
      (node (ref "U$2") (pin "18/A4/SDA") (pinfunction "18/A4/SDA_18/A4/SDA") (pintype "bidirectional"))
    )
    (net (code "78") (name "Net-(U$2-Pad3V3_LO)") (class "Default")
      (node (ref "U$2") (pin "3V3_LO") (pinfunction "3V3_LO_3V3_LO") (pintype "bidirectional"))
      (node (ref "U$2") (pin "AREF") (pinfunction "AREF_AREF") (pintype "bidirectional"))
    )
    (net (code "79") (name "Net-(U$3-BLUE)") (class "Default")
      (node (ref "R1") (pin "2") (pinfunction "2_2") (pintype "passive"))
      (node (ref "U$3") (pin "1") (pinfunction "BLUE_1") (pintype "bidirectional"))
    )
    (net (code "80") (name "Net-(U$3-GREEN)") (class "Default")
      (node (ref "R2") (pin "2") (pinfunction "2_2") (pintype "passive"))
      (node (ref "U$3") (pin "2") (pinfunction "GREEN_2") (pintype "bidirectional"))
    )
    (net (code "81") (name "Net-(U$3-RED)") (class "Default")
      (node (ref "R3") (pin "2") (pinfunction "2_2") (pintype "passive"))
      (node (ref "U$3") (pin "4") (pinfunction "RED_4") (pintype "bidirectional"))
    )
    (net (code "82") (name "Net-(U$4-BLUE)") (class "Default")
      (node (ref "R4") (pin "2") (pinfunction "2_2") (pintype "passive"))
      (node (ref "U$4") (pin "1") (pinfunction "BLUE_1") (pintype "bidirectional"))
    )
    (net (code "83") (name "Net-(U$4-GREEN)") (class "Default")
      (node (ref "R5") (pin "2") (pinfunction "2_2") (pintype "passive"))
      (node (ref "U$4") (pin "2") (pinfunction "GREEN_2") (pintype "bidirectional"))
    )
    (net (code "84") (name "Net-(U$4-RED)") (class "Default")
      (node (ref "R6") (pin "2") (pinfunction "2_2") (pintype "passive"))
      (node (ref "U$4") (pin "4") (pinfunction "RED_4") (pintype "bidirectional"))
    )
    (net (code "85") (name "VCC") (class "Default")
      (node (ref "B1") (pin "HV") (pinfunction "HV_HV") (pintype "power_in"))
      (node (ref "B2") (pin "HV") (pinfunction "HV_HV") (pintype "power_in"))
      (node (ref "B3") (pin "HV") (pinfunction "HV_HV") (pintype "power_in"))
      (node (ref "B4") (pin "HV") (pinfunction "HV_HV") (pintype "power_in"))
      (node (ref "B5") (pin "HV") (pinfunction "HV_HV") (pintype "power_in"))
      (node (ref "B6") (pin "HV") (pinfunction "HV_HV") (pintype "power_in"))
      (node (ref "C1") (pin "2") (pinfunction "2_2") (pintype "passive"))
      (node (ref "C10") (pin "+") (pinfunction "+_+") (pintype "passive"))
      (node (ref "C11") (pin "1") (pinfunction "1_1") (pintype "passive"))
      (node (ref "C4") (pin "2") (pinfunction "2_2") (pintype "passive"))
      (node (ref "C5") (pin "2") (pinfunction "2_2") (pintype "passive"))
      (node (ref "C6") (pin "2") (pinfunction "2_2") (pintype "passive"))
      (node (ref "C7") (pin "2") (pinfunction "2_2") (pintype "passive"))
      (node (ref "IC1") (pin "14") (pinfunction "VCC_14") (pintype "power_in"))
      (node (ref "IC10") (pin "14") (pinfunction "VCC_14") (pintype "power_in"))
      (node (ref "IC3") (pin "14") (pinfunction "VCC_14") (pintype "power_in"))
      (node (ref "IC4") (pin "20") (pinfunction "VCC_20") (pintype "power_in"))
      (node (ref "IC5") (pin "14") (pinfunction "VCC_14") (pintype "power_in"))
      (node (ref "IC9") (pin "3") (pinfunction "VO_3") (pintype "passive"))
      (node (ref "U$2") (pin "VIN") (pinfunction "VIN_VIN") (pintype "bidirectional"))
    )
    (net (code "86") (name "VCC{slash}2") (class "Default")
      (node (ref "B1") (pin "LV") (pinfunction "LV_LV") (pintype "power_in"))
      (node (ref "B2") (pin "LV") (pinfunction "LV_LV") (pintype "power_in"))
      (node (ref "B3") (pin "LV") (pinfunction "LV_LV") (pintype "power_in"))
      (node (ref "B4") (pin "LV") (pinfunction "LV_LV") (pintype "power_in"))
      (node (ref "B5") (pin "LV") (pinfunction "LV_LV") (pintype "power_in"))
      (node (ref "B6") (pin "LV") (pinfunction "LV_LV") (pintype "power_in"))
      (node (ref "U$2") (pin "3V3_2") (pinfunction "3V3_2_3V3_2") (pintype "bidirectional"))
    )
    (net (code "87") (name "unconnected-(B2-HV_RXI_2-PadHV3)") (class "Default")
      (node (ref "B2") (pin "HV3") (pinfunction "HV_RXI_2_HV3") (pintype "bidirectional"))
    )
    (net (code "88") (name "unconnected-(B2-HV_TXO_2-PadHV4)") (class "Default")
      (node (ref "B2") (pin "HV4") (pinfunction "HV_TXO_2_HV4") (pintype "bidirectional"))
    )
    (net (code "89") (name "unconnected-(B2-LV_RXO_2-PadLV3)") (class "Default")
      (node (ref "B2") (pin "LV3") (pinfunction "LV_RXO_2_LV3") (pintype "bidirectional"))
    )
    (net (code "90") (name "unconnected-(B2-LV_TXI_2-PadLV4)") (class "Default")
      (node (ref "B2") (pin "LV4") (pinfunction "LV_TXI_2_LV4") (pintype "bidirectional"))
    )
    (net (code "91") (name "unconnected-(IC1C-O-Pad8)") (class "Default")
      (node (ref "IC1") (pin "8") (pinfunction "O_8") (pintype "output"))
    )
    (net (code "92") (name "unconnected-(IC1D-O-Pad11)") (class "Default")
      (node (ref "IC1") (pin "11") (pinfunction "O_11") (pintype "output"))
    )
    (net (code "93") (name "unconnected-(IC5A-Q-Pad5)") (class "Default")
      (node (ref "IC5") (pin "5") (pinfunction "Q_5") (pintype "output"))
    )
    (net (code "94") (name "unconnected-(IC5B-Q-Pad9)") (class "Default")
      (node (ref "IC5") (pin "9") (pinfunction "Q_9") (pintype "output"))
    )
    (net (code "95") (name "unconnected-(IC5B-~{Q}-Pad8)") (class "Default")
      (node (ref "IC5") (pin "8") (pinfunction "~{Q}_8") (pintype "output"))
    )
    (net (code "96") (name "unconnected-(U$1-CAS*-PadP$3)") (class "Default")
      (node (ref "U$1") (pin "P$3") (pinfunction "CAS*_P$3") (pintype "bidirectional"))
    )
    (net (code "97") (name "unconnected-(U$1-IN*-PadP$19)") (class "Default")
      (node (ref "U$1") (pin "P$19") (pinfunction "IN*_P$19") (pintype "bidirectional"))
    )
    (net (code "98") (name "unconnected-(U$1-INT*-PadP$21)") (class "Default")
      (node (ref "U$1") (pin "P$21") (pinfunction "INT*_P$21") (pintype "bidirectional"))
    )
    (net (code "99") (name "unconnected-(U$1-INTAK*-PadP$14)") (class "Default")
      (node (ref "U$1") (pin "P$14") (pinfunction "INTAK*_P$14") (pintype "bidirectional"))
    )
    (net (code "100") (name "unconnected-(U$1-MUX-PadP$16)") (class "Default")
      (node (ref "U$1") (pin "P$16") (pinfunction "MUX_P$16") (pintype "bidirectional"))
    )
    (net (code "101") (name "unconnected-(U$1-NC-PadP$39)") (class "Default")
      (node (ref "U$1") (pin "P$39") (pinfunction "NC_P$39") (pintype "bidirectional"))
    )
    (net (code "102") (name "unconnected-(U$1-OUT*-PadP$12)") (class "Default")
      (node (ref "U$1") (pin "P$12") (pinfunction "OUT*_P$12") (pintype "bidirectional"))
    )
    (net (code "103") (name "unconnected-(U$1-RAS*-PadP$1)") (class "Default")
      (node (ref "U$1") (pin "P$1") (pinfunction "RAS*_P$1") (pintype "bidirectional"))
    )
    (net (code "104") (name "unconnected-(U$1-SYSRES*-PadP$2)") (class "Default")
      (node (ref "U$1") (pin "P$2") (pinfunction "SYSRES*_P$2") (pintype "bidirectional"))
    )
    (net (code "105") (name "unconnected-(U$1-TEST*-PadP$23)") (class "Default")
      (node (ref "U$1") (pin "P$23") (pinfunction "TEST*_P$23") (pintype "bidirectional"))
    )
    (net (code "106") (name "unconnected-(U$2-Pad0{slash}RX)") (class "Default")
      (node (ref "U$2") (pin "0/RX") (pinfunction "0/RX_0/RX") (pintype "bidirectional"))
    )
    (net (code "107") (name "unconnected-(U$2-Pad1{slash}TX)") (class "Default")
      (node (ref "U$2") (pin "1/TX") (pinfunction "1/TX_1/TX") (pintype "bidirectional"))
    )
    (net (code "108") (name "unconnected-(U$2-Pad3V3)") (class "Default")
      (node (ref "U$2") (pin "3V3") (pinfunction "3V3_3V3") (pintype "bidirectional"))
    )
    (net (code "109") (name "unconnected-(U$2-Pad10{slash}CS)") (class "Default")
      (node (ref "U$2") (pin "10/CS") (pinfunction "10/CS_10/CS") (pintype "bidirectional"))
    )
    (net (code "110") (name "unconnected-(U$2-Pad11{slash}MOSI)") (class "Default")
      (node (ref "U$2") (pin "11/MOSI") (pinfunction "11/MOSI_11/MOSI") (pintype "bidirectional"))
    )
    (net (code "111") (name "unconnected-(U$2-Pad12{slash}MISO)") (class "Default")
      (node (ref "U$2") (pin "12/MISO") (pinfunction "12/MISO_12/MISO") (pintype "bidirectional"))
    )
    (net (code "112") (name "unconnected-(U$2-Pad13{slash}SCK)") (class "Default")
      (node (ref "U$2") (pin "13/SCK") (pinfunction "13/SCK_13/SCK") (pintype "bidirectional"))
    )
    (net (code "113") (name "unconnected-(U$2-Pad14{slash}A0)") (class "Default")
      (node (ref "U$2") (pin "14/A0") (pinfunction "14/A0_14/A0") (pintype "bidirectional"))
    )
    (net (code "114") (name "unconnected-(U$2-Pad15{slash}A1)") (class "Default")
      (node (ref "U$2") (pin "15/A1") (pinfunction "15/A1_15/A1") (pintype "bidirectional"))
    )
    (net (code "115") (name "unconnected-(U$2-Pad16{slash}A2)") (class "Default")
      (node (ref "U$2") (pin "16/A2") (pinfunction "16/A2_16/A2") (pintype "bidirectional"))
    )
    (net (code "116") (name "unconnected-(U$2-Pad17{slash}A3)") (class "Default")
      (node (ref "U$2") (pin "17/A3") (pinfunction "17/A3_17/A3") (pintype "bidirectional"))
    )
    (net (code "117") (name "unconnected-(U$2-Pad30)") (class "Default")
      (node (ref "U$2") (pin "30") (pinfunction "30_30") (pintype "bidirectional"))
    )
    (net (code "118") (name "unconnected-(U$2-Pad31{slash}A12)") (class "Default")
      (node (ref "U$2") (pin "31/A12") (pinfunction "31/A12_31/A12") (pintype "bidirectional"))
    )
    (net (code "119") (name "unconnected-(U$2-Pad32{slash}A13)") (class "Default")
      (node (ref "U$2") (pin "32/A13") (pinfunction "32/A13_32/A13") (pintype "bidirectional"))
    )
    (net (code "120") (name "unconnected-(U$2-PadA10)") (class "Default")
      (node (ref "U$2") (pin "A10") (pinfunction "A10_A10") (pintype "bidirectional"))
    )
    (net (code "121") (name "unconnected-(U$2-PadA11)") (class "Default")
      (node (ref "U$2") (pin "A11") (pinfunction "A11_A11") (pintype "bidirectional"))
    )
    (net (code "122") (name "unconnected-(U$2-PadA22{slash}DAC1)") (class "Default")
      (node (ref "U$2") (pin "A22/DAC1") (pinfunction "A22/DAC1_A22/DAC1") (pintype "bidirectional"))
    )
    (net (code "123") (name "unconnected-(U$2-PadPROG)") (class "Default")
      (node (ref "U$2") (pin "PROG") (pinfunction "PROG_PROG") (pintype "bidirectional"))
    )
    (net (code "124") (name "unconnected-(U$2-PadRESET)") (class "Default")
      (node (ref "U$2") (pin "RESET") (pinfunction "RESET_RESET") (pintype "bidirectional"))
    )
    (net (code "125") (name "unconnected-(U$2-PadU5V)") (class "Default")
      (node (ref "U$2") (pin "U5V") (pinfunction "U5V_U5V") (pintype "bidirectional"))
    )
    (net (code "126") (name "unconnected-(U$2-PadUD+)") (class "Default")
      (node (ref "U$2") (pin "UD+") (pinfunction "UD+_UD+") (pintype "bidirectional"))
    )
    (net (code "127") (name "unconnected-(U$2-PadUD-)") (class "Default")
      (node (ref "U$2") (pin "UD-") (pinfunction "UD-_UD-") (pintype "bidirectional"))
    )
    (net (code "128") (name "unconnected-(U$2-PadVBAT)") (class "Default")
      (node (ref "U$2") (pin "VBAT") (pinfunction "VBAT_VBAT") (pintype "bidirectional"))
    )
    (net (code "129") (name "unconnected-(U$2-PadVUSB)") (class "Default")
      (node (ref "U$2") (pin "VUSB") (pinfunction "VUSB_VUSB") (pintype "bidirectional"))
    )
  )
)
